# Console_Block.net
KiCad netlist of a schematic drawn in EAGLE
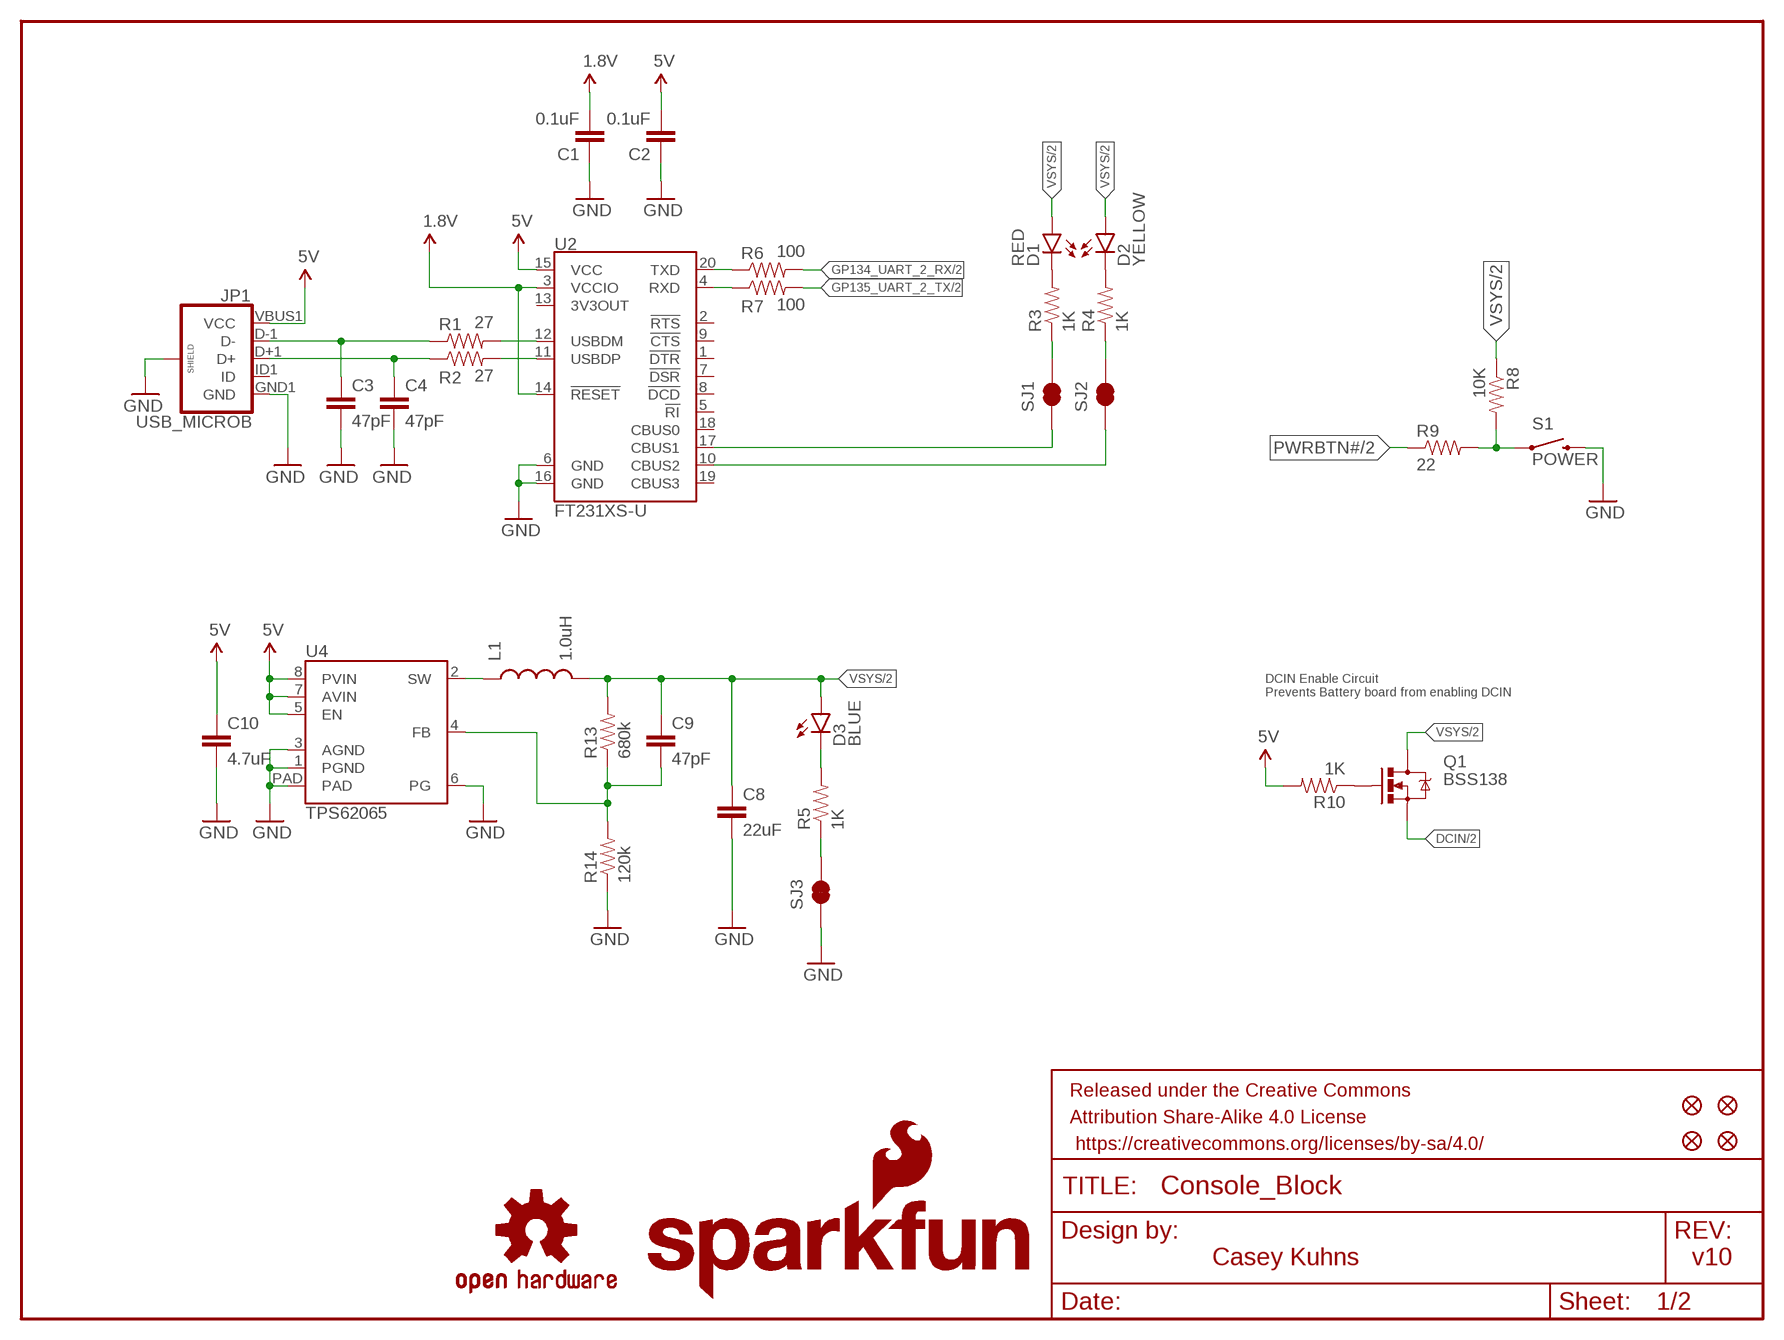
[diagram p0: schematic, sheet 1]
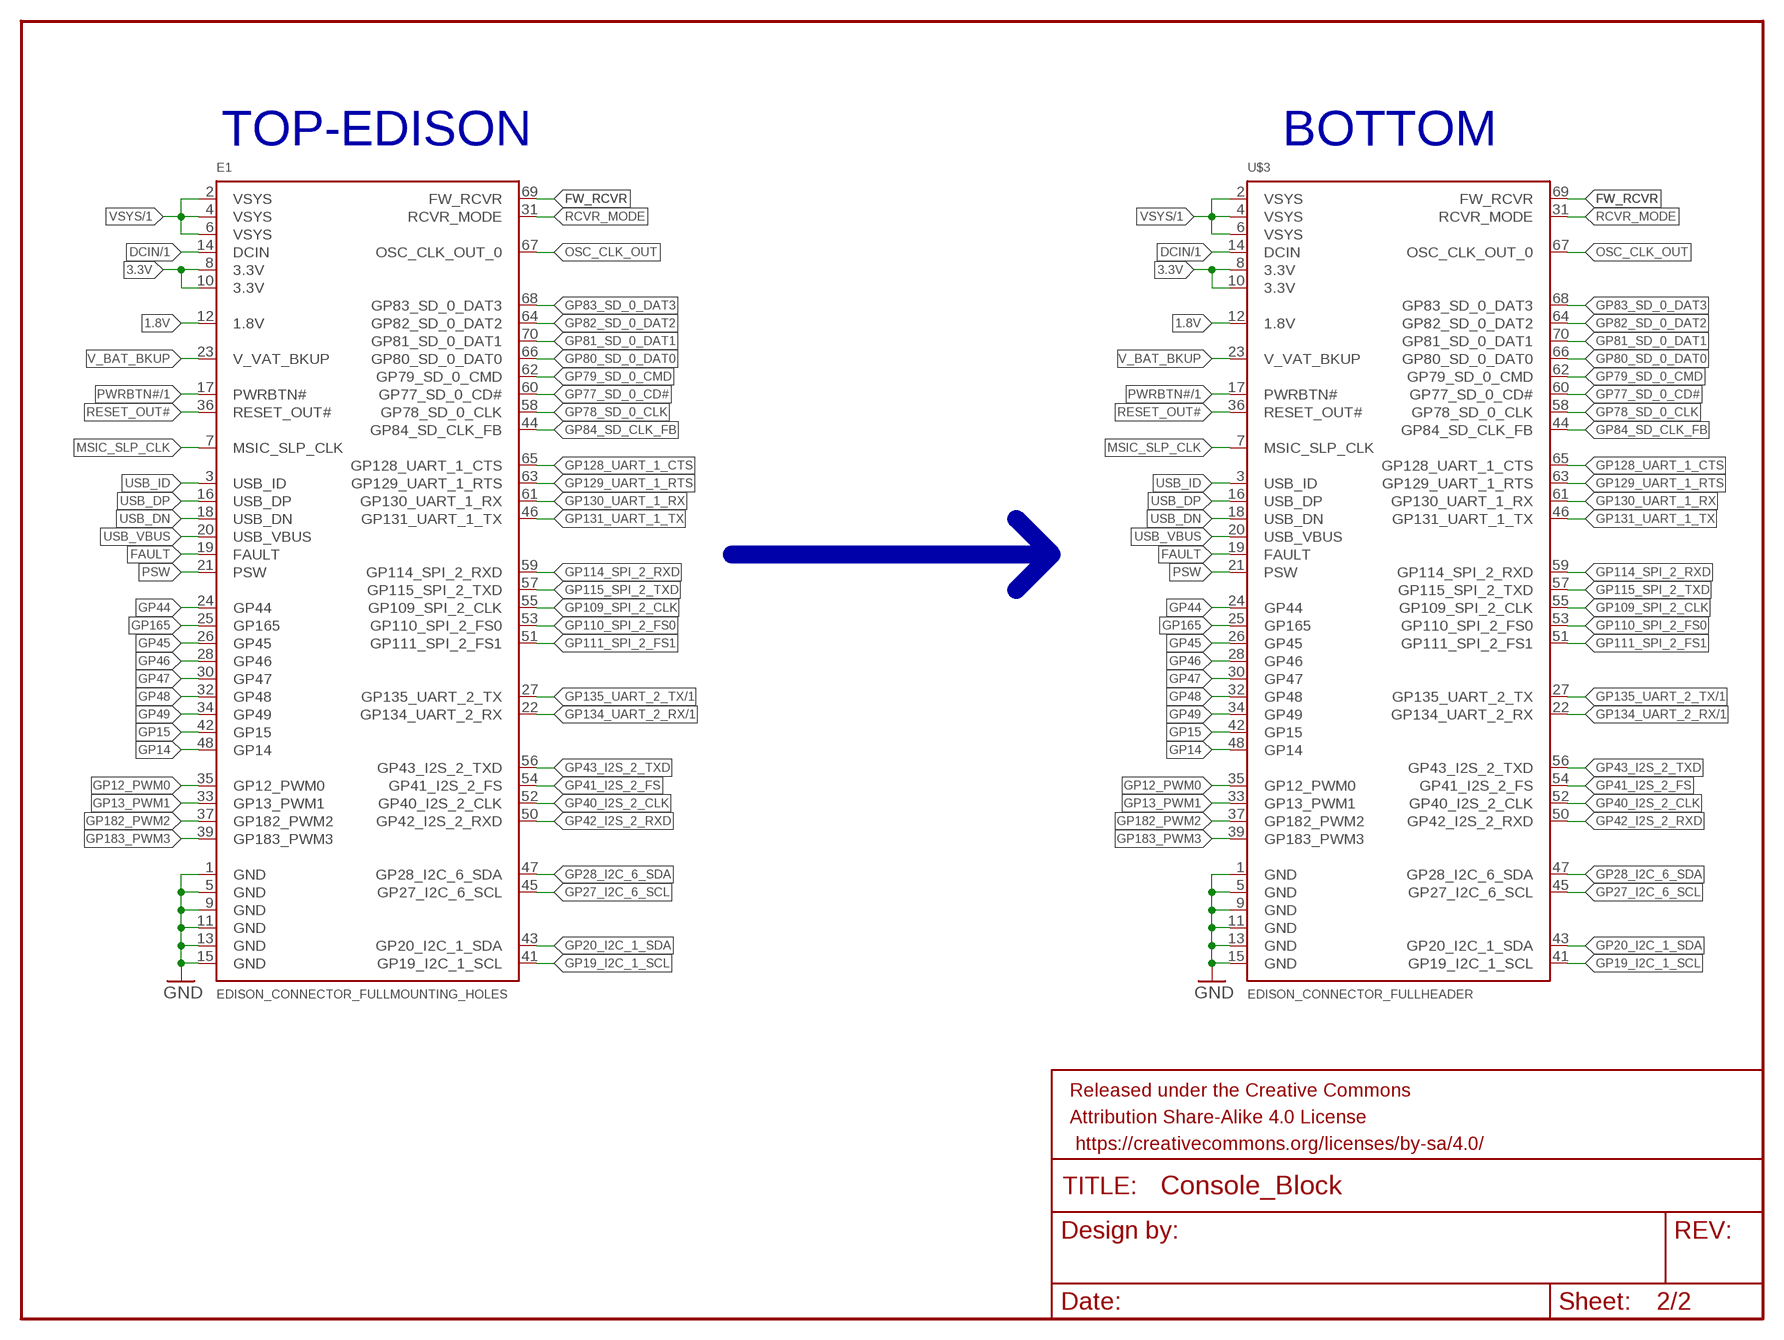
[diagram p1: schematic, sheet 2]

(export (version "E")
  (design (tool "Eeschema 10.0.6"))
  (components
    (comp (ref "E1")
      (value "EDISON_CONNECTOR_FULLMOUNTING_HOLES")
      (footprint "eagle-import:EDISON_DAUGHTER")
      (libsource (lib "eagle-import") (part "EDISON_CONNECTOR_FULLMOUNTING_HOLES"))
    )
    (comp (ref "FRAME2")
      (value "FRAME-LETTER")
      (footprint "eagle-import:CREATIVE_COMMONS")
      (libsource (lib "eagle-import") (part "FRAME-LETTER"))
    )
    (comp (ref "U$3")
      (value "EDISON_CONNECTOR_FULLHEADER")
      (footprint "eagle-import:DF40C-70DP-0.4(51)")
      (libsource (lib "eagle-import") (part "EDISON_CONNECTOR_FULLHEADER"))
    )
    (comp (ref "C1")
      (value "0.1uF")
      (footprint "eagle-import:0603-CAP")
      (libsource (lib "eagle-import") (part "0.1UF-25V-5%(0603)"))
    )
    (comp (ref "C2")
      (value "0.1uF")
      (footprint "eagle-import:0603-CAP")
      (libsource (lib "eagle-import") (part "0.1UF-25V-5%(0603)"))
    )
    (comp (ref "C3")
      (value "47pF")
      (footprint "eagle-import:0603-CAP")
      (libsource (lib "eagle-import") (part "47PF-50V-5%(0603)"))
    )
    (comp (ref "C4")
      (value "47pF")
      (footprint "eagle-import:0603-CAP")
      (libsource (lib "eagle-import") (part "47PF-50V-5%(0603)"))
    )
    (comp (ref "C8")
      (value "22uF")
      (footprint "eagle-import:0805")
      (libsource (lib "eagle-import") (part "22UF-6.3V-20%(0805)"))
    )
    (comp (ref "C9")
      (value "47pF")
      (footprint "eagle-import:0603-CAP")
      (libsource (lib "eagle-import") (part "47PF-50V-5%(0603)"))
    )
    (comp (ref "C10")
      (value "4.7uF")
      (footprint "eagle-import:0603-CAP")
      (libsource (lib "eagle-import") (part "4.7UF-6.3V-10%(0603)0603"))
    )
    (comp (ref "D1")
      (value "RED")
      (footprint "eagle-import:LED-0603")
      (libsource (lib "eagle-import") (part "LED-RED0603"))
    )
    (comp (ref "D2")
      (value "YELLOW")
      (footprint "eagle-import:LED-0603")
      (libsource (lib "eagle-import") (part "LED-YELLOW0603"))
    )
    (comp (ref "D3")
      (value "BLUE")
      (footprint "eagle-import:LED-0603")
      (libsource (lib "eagle-import") (part "LED-BLUE0603"))
    )
    (comp (ref "FID1")
      (value "FIDUCIAL1X2")
      (footprint "eagle-import:FIDUCIAL-1X2")
      (libsource (lib "eagle-import") (part "FIDUCIAL1X2"))
    )
    (comp (ref "FID2")
      (value "FIDUCIAL1X2")
      (footprint "eagle-import:FIDUCIAL-1X2")
      (libsource (lib "eagle-import") (part "FIDUCIAL1X2"))
    )
    (comp (ref "FID3")
      (value "FIDUCIAL1X2")
      (footprint "eagle-import:FIDUCIAL-1X2")
      (libsource (lib "eagle-import") (part "FIDUCIAL1X2"))
    )
    (comp (ref "FID4")
      (value "FIDUCIAL1X2")
      (footprint "eagle-import:FIDUCIAL-1X2")
      (libsource (lib "eagle-import") (part "FIDUCIAL1X2"))
    )
    (comp (ref "FRAME1")
      (value "FRAME-LETTER")
      (footprint "eagle-import:CREATIVE_COMMONS")
      (libsource (lib "eagle-import") (part "FRAME-LETTER"))
    )
    (comp (ref "JP1")
      (value "USB_MICROB")
      (footprint "eagle-import:USB-B-MICRO-SMD_V03")
      (libsource (lib "eagle-import") (part "USB_MICROB_PLUGCONN-11752"))
    )
    (comp (ref "L1")
      (value "1.0uH")
      (footprint "eagle-import:INDUCTOR-SRP4020")
      (libsource (lib "eagle-import") (part "INDUCTOR"))
    )
    (comp (ref "LOGO1")
      (value "SFE_LOGO_NAME_FLAME.1_INCH")
      (footprint "eagle-import:SFE_LOGO_NAME_FLAME_.1")
      (libsource (lib "eagle-import") (part "SFE_LOGO_NAME_FLAME.1_INCH"))
    )
    (comp (ref "LOGO4")
      (value "OSHW-LOGOS")
      (footprint "eagle-import:OSHW-LOGO-S")
      (libsource (lib "eagle-import") (part "OSHW-LOGOS"))
    )
    (comp (ref "Q1")
      (value "BSS138")
      (footprint "eagle-import:SOT23-3")
      (libsource (lib "eagle-import") (part "MOSFET-NCHANNELBSS138"))
    )
    (comp (ref "R1")
      (value "27")
      (footprint "eagle-import:0603")
      (libsource (lib "eagle-import") (part "27OHM1/10W1%(0603)"))
    )
    (comp (ref "R2")
      (value "27")
      (footprint "eagle-import:0603")
      (libsource (lib "eagle-import") (part "27OHM1/10W1%(0603)"))
    )
    (comp (ref "R3")
      (value "1K")
      (footprint "eagle-import:0603-RES")
      (libsource (lib "eagle-import") (part "1KOHM1/10W1%(0603)"))
    )
    (comp (ref "R4")
      (value "1K")
      (footprint "eagle-import:0603-RES")
      (libsource (lib "eagle-import") (part "1KOHM1/10W1%(0603)"))
    )
    (comp (ref "R5")
      (value "1K")
      (footprint "eagle-import:0603-RES")
      (libsource (lib "eagle-import") (part "1KOHM1/10W1%(0603)"))
    )
    (comp (ref "R6")
      (value "100")
      (footprint "eagle-import:0603-RES")
      (libsource (lib "eagle-import") (part "100OHM1/10W1%(0603)"))
    )
    (comp (ref "R7")
      (value "100")
      (footprint "eagle-import:0603-RES")
      (libsource (lib "eagle-import") (part "100OHM1/10W1%(0603)"))
    )
    (comp (ref "R8")
      (value "10K")
      (footprint "eagle-import:0603-RES")
      (libsource (lib "eagle-import") (part "10KOHM1/10W1%(0603)0603"))
    )
    (comp (ref "R9")
      (value "22")
      (footprint "eagle-import:0603-RES")
      (libsource (lib "eagle-import") (part "22OHM1/10W1%(0603)"))
    )
    (comp (ref "R10")
      (value "1K")
      (footprint "eagle-import:0603-RES")
      (libsource (lib "eagle-import") (part "1KOHM1/10W1%(0603)"))
    )
    (comp (ref "R13")
      (value "680k")
      (footprint "eagle-import:0603-RES")
      (libsource (lib "eagle-import") (part "RESISTOR0603"))
    )
    (comp (ref "R14")
      (value "120k")
      (footprint "eagle-import:0603-RES")
      (libsource (lib "eagle-import") (part "RESISTOR0603"))
    )
    (comp (ref "S1")
      (value "POWER")
      (footprint "eagle-import:TACTILE_SWITCH-SMD-RIGHT-ANGLE")
      (libsource (lib "eagle-import") (part "SWITCH-MOMENTARY-2TACTILE-SWITCH-SMD-RIGHT-ANGLE"))
    )
    (comp (ref "SJ1")
      (value "JUMPER-PAD-2-NC_BY_TRACE")
      (footprint "eagle-import:PAD-JUMPER-2-NC_BY_TRACE_YES_SILK")
      (libsource (lib "eagle-import") (part "JUMPER-PAD-2-NC_BY_TRACE"))
    )
    (comp (ref "SJ2")
      (value "JUMPER-PAD-2-NC_BY_TRACE")
      (footprint "eagle-import:PAD-JUMPER-2-NC_BY_TRACE_YES_SILK")
      (libsource (lib "eagle-import") (part "JUMPER-PAD-2-NC_BY_TRACE"))
    )
    (comp (ref "SJ3")
      (value "JUMPER-PAD-2-NC_BY_TRACE")
      (footprint "eagle-import:PAD-JUMPER-2-NC_BY_TRACE_YES_SILK")
      (libsource (lib "eagle-import") (part "JUMPER-PAD-2-NC_BY_TRACE"))
    )
    (comp (ref "U2")
      (value "FT231XS-U")
      (footprint "eagle-import:SSOP20_L")
      (libsource (lib "eagle-import") (part "FT231XS"))
    )
    (comp (ref "U4")
      (value "TPS62065")
      (footprint "eagle-import:WSON-8-PAD")
      (libsource (lib "eagle-import") (part "TPS62065"))
    )
  )
  (nets
    (net (code "1") (name "1.8V") (class "Default")
      (node (ref "C1") (pin "2") (pinfunction "2_2") (pintype "passive"))
      (node (ref "E1") (pin "12") (pinfunction "1.8V_12") (pintype "bidirectional"))
      (node (ref "U$3") (pin "12") (pinfunction "1.8V_12") (pintype "bidirectional"))
      (node (ref "U2") (pin "14") (pinfunction "~{RESET}_14") (pintype "bidirectional"))
      (node (ref "U2") (pin "3") (pinfunction "VCCIO_3") (pintype "bidirectional"))
    )
    (net (code "2") (name "3.3V") (class "Default")
      (node (ref "E1") (pin "10") (pinfunction "3.3V_10") (pintype "bidirectional"))
      (node (ref "E1") (pin "8") (pinfunction "3.3V_8") (pintype "bidirectional"))
      (node (ref "U$3") (pin "10") (pinfunction "3.3V_10") (pintype "bidirectional"))
      (node (ref "U$3") (pin "8") (pinfunction "3.3V_8") (pintype "bidirectional"))
    )
    (net (code "3") (name "5V") (class "Default")
      (node (ref "C10") (pin "1") (pinfunction "1_1") (pintype "passive"))
      (node (ref "C2") (pin "2") (pinfunction "2_2") (pintype "passive"))
      (node (ref "JP1") (pin "VBUS1") (pinfunction "VCC_VBUS1") (pintype "bidirectional"))
      (node (ref "R10") (pin "2") (pinfunction "2_2") (pintype "passive"))
      (node (ref "U2") (pin "15") (pinfunction "VCC_15") (pintype "bidirectional"))
      (node (ref "U4") (pin "5") (pinfunction "EN_5") (pintype "bidirectional"))
      (node (ref "U4") (pin "7") (pinfunction "AVIN_7") (pintype "bidirectional"))
      (node (ref "U4") (pin "8") (pinfunction "PVIN_8") (pintype "bidirectional"))
    )
    (net (code "4") (name "DCIN") (class "Default")
      (node (ref "E1") (pin "14") (pinfunction "DCIN_14") (pintype "bidirectional"))
      (node (ref "Q1") (pin "2") (pinfunction "S_2") (pintype "passive"))
      (node (ref "U$3") (pin "14") (pinfunction "DCIN_14") (pintype "bidirectional"))
    )
    (net (code "5") (name "FAULT") (class "Default")
      (node (ref "E1") (pin "19") (pinfunction "FAULT_19") (pintype "bidirectional"))
      (node (ref "U$3") (pin "19") (pinfunction "FAULT_19") (pintype "bidirectional"))
    )
    (net (code "6") (name "FW_RCVR") (class "Default")
      (node (ref "E1") (pin "69") (pinfunction "FW_RCVR_69") (pintype "bidirectional"))
      (node (ref "U$3") (pin "69") (pinfunction "FW_RCVR_69") (pintype "bidirectional"))
    )
    (net (code "7") (name "GND") (class "Default")
      (node (ref "C1") (pin "1") (pinfunction "1_1") (pintype "passive"))
      (node (ref "C10") (pin "2") (pinfunction "2_2") (pintype "passive"))
      (node (ref "C2") (pin "1") (pinfunction "1_1") (pintype "passive"))
      (node (ref "C3") (pin "2") (pinfunction "2_2") (pintype "passive"))
      (node (ref "C4") (pin "2") (pinfunction "2_2") (pintype "passive"))
      (node (ref "C8") (pin "2") (pinfunction "2_2") (pintype "passive"))
      (node (ref "E1") (pin "1") (pinfunction "GND_1") (pintype "bidirectional"))
      (node (ref "E1") (pin "11") (pinfunction "GND_11") (pintype "bidirectional"))
      (node (ref "E1") (pin "13") (pinfunction "GND_13") (pintype "bidirectional"))
      (node (ref "E1") (pin "15") (pinfunction "GND_15") (pintype "bidirectional"))
      (node (ref "E1") (pin "5") (pinfunction "GND_5") (pintype "bidirectional"))
      (node (ref "E1") (pin "9") (pinfunction "GND_9") (pintype "bidirectional"))
      (node (ref "JP1") (pin "GND1") (pinfunction "GND_GND1") (pintype "bidirectional"))
      (node (ref "JP1") (pin "SHIELD1") (pinfunction "SHIELD_SHIELD1") (pintype "bidirectional"))
      (node (ref "JP1") (pin "SHIELD2") (pinfunction "SHIELD_SHIELD2") (pintype "bidirectional"))
      (node (ref "JP1") (pin "SHIELD3") (pinfunction "SHIELD_SHIELD3") (pintype "bidirectional"))
      (node (ref "R14") (pin "1") (pinfunction "1_1") (pintype "passive"))
      (node (ref "S1") (pin "2") (pinfunction "2_2") (pintype "passive"))
      (node (ref "SJ3") (pin "1") (pinfunction "1_1") (pintype "passive"))
      (node (ref "U$3") (pin "1") (pinfunction "GND_1") (pintype "bidirectional"))
      (node (ref "U$3") (pin "11") (pinfunction "GND_11") (pintype "bidirectional"))
      (node (ref "U$3") (pin "13") (pinfunction "GND_13") (pintype "bidirectional"))
      (node (ref "U$3") (pin "15") (pinfunction "GND_15") (pintype "bidirectional"))
      (node (ref "U$3") (pin "5") (pinfunction "GND_5") (pintype "bidirectional"))
      (node (ref "U$3") (pin "9") (pinfunction "GND_9") (pintype "bidirectional"))
      (node (ref "U2") (pin "16") (pinfunction "GND_16") (pintype "bidirectional"))
      (node (ref "U2") (pin "6") (pinfunction "GND_6") (pintype "bidirectional"))
      (node (ref "U4") (pin "1") (pinfunction "PGND_1") (pintype "bidirectional"))
      (node (ref "U4") (pin "3") (pinfunction "AGND_3") (pintype "bidirectional"))
      (node (ref "U4") (pin "6") (pinfunction "PG_6") (pintype "bidirectional"))
      (node (ref "U4") (pin "PAD") (pinfunction "PAD_PAD") (pintype "bidirectional"))
    )
    (net (code "8") (name "GP12_PWM0") (class "Default")
      (node (ref "E1") (pin "35") (pinfunction "GP12_PWM0_35") (pintype "bidirectional"))
      (node (ref "U$3") (pin "35") (pinfunction "GP12_PWM0_35") (pintype "bidirectional"))
    )
    (net (code "9") (name "GP13_PWM1") (class "Default")
      (node (ref "E1") (pin "33") (pinfunction "GP13_PWM1_33") (pintype "bidirectional"))
      (node (ref "U$3") (pin "33") (pinfunction "GP13_PWM1_33") (pintype "bidirectional"))
    )
    (net (code "10") (name "GP14") (class "Default")
      (node (ref "E1") (pin "48") (pinfunction "GP14_48") (pintype "bidirectional"))
      (node (ref "U$3") (pin "48") (pinfunction "GP14_48") (pintype "bidirectional"))
    )
    (net (code "11") (name "GP15") (class "Default")
      (node (ref "E1") (pin "42") (pinfunction "GP15_42") (pintype "bidirectional"))
      (node (ref "U$3") (pin "42") (pinfunction "GP15_42") (pintype "bidirectional"))
    )
    (net (code "12") (name "GP19_I2C_1_SCL") (class "Default")
      (node (ref "E1") (pin "41") (pinfunction "GP19_I2C_1_SCL_41") (pintype "bidirectional"))
      (node (ref "U$3") (pin "41") (pinfunction "GP19_I2C_1_SCL_41") (pintype "bidirectional"))
    )
    (net (code "13") (name "GP20_I2C_1_SDA") (class "Default")
      (node (ref "E1") (pin "43") (pinfunction "GP20_I2C_1_SDA_43") (pintype "bidirectional"))
      (node (ref "U$3") (pin "43") (pinfunction "GP20_I2C_1_SDA_43") (pintype "bidirectional"))
    )
    (net (code "14") (name "GP27_I2C_6_SCL") (class "Default")
      (node (ref "E1") (pin "45") (pinfunction "GP27_I2C_6_SCL_45") (pintype "bidirectional"))
      (node (ref "U$3") (pin "45") (pinfunction "GP27_I2C_6_SCL_45") (pintype "bidirectional"))
    )
    (net (code "15") (name "GP28_I2C_6_SDA") (class "Default")
      (node (ref "E1") (pin "47") (pinfunction "GP28_I2C_6_SDA_47") (pintype "bidirectional"))
      (node (ref "U$3") (pin "47") (pinfunction "GP28_I2C_6_SDA_47") (pintype "bidirectional"))
    )
    (net (code "16") (name "GP40_I2S_2_CLK") (class "Default")
      (node (ref "E1") (pin "52") (pinfunction "GP40_I2S_2_CLK_52") (pintype "bidirectional"))
      (node (ref "U$3") (pin "52") (pinfunction "GP40_I2S_2_CLK_52") (pintype "bidirectional"))
    )
    (net (code "17") (name "GP41_I2S_2_FS") (class "Default")
      (node (ref "E1") (pin "54") (pinfunction "GP41_I2S_2_FS_54") (pintype "bidirectional"))
      (node (ref "U$3") (pin "54") (pinfunction "GP41_I2S_2_FS_54") (pintype "bidirectional"))
    )
    (net (code "18") (name "GP42_I2S_2_RXD") (class "Default")
      (node (ref "E1") (pin "50") (pinfunction "GP42_I2S_2_RXD_50") (pintype "bidirectional"))
      (node (ref "U$3") (pin "50") (pinfunction "GP42_I2S_2_RXD_50") (pintype "bidirectional"))
    )
    (net (code "19") (name "GP43_I2S_2_TXD") (class "Default")
      (node (ref "E1") (pin "56") (pinfunction "GP43_I2S_2_TXD_56") (pintype "bidirectional"))
      (node (ref "U$3") (pin "56") (pinfunction "GP43_I2S_2_TXD_56") (pintype "bidirectional"))
    )
    (net (code "20") (name "GP44") (class "Default")
      (node (ref "E1") (pin "24") (pinfunction "GP44_24") (pintype "bidirectional"))
      (node (ref "U$3") (pin "24") (pinfunction "GP44_24") (pintype "bidirectional"))
    )
    (net (code "21") (name "GP45") (class "Default")
      (node (ref "E1") (pin "26") (pinfunction "GP45_26") (pintype "bidirectional"))
      (node (ref "U$3") (pin "26") (pinfunction "GP45_26") (pintype "bidirectional"))
    )
    (net (code "22") (name "GP46") (class "Default")
      (node (ref "E1") (pin "28") (pinfunction "GP46_28") (pintype "bidirectional"))
      (node (ref "U$3") (pin "28") (pinfunction "GP46_28") (pintype "bidirectional"))
    )
    (net (code "23") (name "GP47") (class "Default")
      (node (ref "E1") (pin "30") (pinfunction "GP47_30") (pintype "bidirectional"))
      (node (ref "U$3") (pin "30") (pinfunction "GP47_30") (pintype "bidirectional"))
    )
    (net (code "24") (name "GP48") (class "Default")
      (node (ref "E1") (pin "32") (pinfunction "GP48_32") (pintype "bidirectional"))
      (node (ref "U$3") (pin "32") (pinfunction "GP48_32") (pintype "bidirectional"))
    )
    (net (code "25") (name "GP49") (class "Default")
      (node (ref "E1") (pin "34") (pinfunction "GP49_34") (pintype "bidirectional"))
      (node (ref "U$3") (pin "34") (pinfunction "GP49_34") (pintype "bidirectional"))
    )
    (net (code "26") (name "GP77_SD_0_CD#") (class "Default")
      (node (ref "E1") (pin "60") (pinfunction "GP77_SD_0_CD#_60") (pintype "bidirectional"))
      (node (ref "U$3") (pin "60") (pinfunction "GP77_SD_0_CD#_60") (pintype "bidirectional"))
    )
    (net (code "27") (name "GP78_SD_0_CLK") (class "Default")
      (node (ref "E1") (pin "58") (pinfunction "GP78_SD_0_CLK_58") (pintype "bidirectional"))
      (node (ref "U$3") (pin "58") (pinfunction "GP78_SD_0_CLK_58") (pintype "bidirectional"))
    )
    (net (code "28") (name "GP79_SD_0_CMD") (class "Default")
      (node (ref "E1") (pin "62") (pinfunction "GP79_SD_0_CMD_62") (pintype "bidirectional"))
      (node (ref "U$3") (pin "62") (pinfunction "GP79_SD_0_CMD_62") (pintype "bidirectional"))
    )
    (net (code "29") (name "GP80_SD_0_DAT0") (class "Default")
      (node (ref "E1") (pin "66") (pinfunction "GP80_SD_0_DAT0_66") (pintype "bidirectional"))
      (node (ref "U$3") (pin "66") (pinfunction "GP80_SD_0_DAT0_66") (pintype "bidirectional"))
    )
    (net (code "30") (name "GP81_SD_0_DAT1") (class "Default")
      (node (ref "E1") (pin "70") (pinfunction "GP81_SD_0_DAT1_70") (pintype "bidirectional"))
      (node (ref "U$3") (pin "70") (pinfunction "GP81_SD_0_DAT1_70") (pintype "bidirectional"))
    )
    (net (code "31") (name "GP82_SD_0_DAT2") (class "Default")
      (node (ref "E1") (pin "64") (pinfunction "GP82_SD_0_DAT2_64") (pintype "bidirectional"))
      (node (ref "U$3") (pin "64") (pinfunction "GP82_SD_0_DAT2_64") (pintype "bidirectional"))
    )
    (net (code "32") (name "GP83_SD_0_DAT3") (class "Default")
      (node (ref "E1") (pin "68") (pinfunction "GP83_SD_0_DAT3_68") (pintype "bidirectional"))
      (node (ref "U$3") (pin "68") (pinfunction "GP83_SD_0_DAT3_68") (pintype "bidirectional"))
    )
    (net (code "33") (name "GP84_SD_CLK_FB") (class "Default")
      (node (ref "E1") (pin "44") (pinfunction "GP84_SD_CLK_FB_44") (pintype "bidirectional"))
      (node (ref "U$3") (pin "44") (pinfunction "GP84_SD_CLK_FB_44") (pintype "bidirectional"))
    )
    (net (code "34") (name "GP109_SPI_2_CLK") (class "Default")
      (node (ref "E1") (pin "55") (pinfunction "GP109_SPI_2_CLK_55") (pintype "bidirectional"))
      (node (ref "U$3") (pin "55") (pinfunction "GP109_SPI_2_CLK_55") (pintype "bidirectional"))
    )
    (net (code "35") (name "GP110_SPI_2_FS0") (class "Default")
      (node (ref "E1") (pin "53") (pinfunction "GP110_SPI_2_FS0_53") (pintype "bidirectional"))
      (node (ref "U$3") (pin "53") (pinfunction "GP110_SPI_2_FS0_53") (pintype "bidirectional"))
    )
    (net (code "36") (name "GP111_SPI_2_FS1") (class "Default")
      (node (ref "E1") (pin "51") (pinfunction "GP111_SPI_2_FS1_51") (pintype "bidirectional"))
      (node (ref "U$3") (pin "51") (pinfunction "GP111_SPI_2_FS1_51") (pintype "bidirectional"))
    )
    (net (code "37") (name "GP114_SPI_2_RXD") (class "Default")
      (node (ref "E1") (pin "59") (pinfunction "GP114_SPI_2_RXD_59") (pintype "bidirectional"))
      (node (ref "U$3") (pin "59") (pinfunction "GP114_SPI_2_RXD_59") (pintype "bidirectional"))
    )
    (net (code "38") (name "GP115_SPI_2_TXD") (class "Default")
      (node (ref "E1") (pin "57") (pinfunction "GP115_SPI_2_TXD_57") (pintype "bidirectional"))
      (node (ref "U$3") (pin "57") (pinfunction "GP115_SPI_2_TXD_57") (pintype "bidirectional"))
    )
    (net (code "39") (name "GP128_UART_1_CTS") (class "Default")
      (node (ref "E1") (pin "65") (pinfunction "GP128_UART_1_CTS_65") (pintype "bidirectional"))
      (node (ref "U$3") (pin "65") (pinfunction "GP128_UART_1_CTS_65") (pintype "bidirectional"))
    )
    (net (code "40") (name "GP129_UART_1_RTS") (class "Default")
      (node (ref "E1") (pin "63") (pinfunction "GP129_UART_1_RTS_63") (pintype "bidirectional"))
      (node (ref "U$3") (pin "63") (pinfunction "GP129_UART_1_RTS_63") (pintype "bidirectional"))
    )
    (net (code "41") (name "GP130_UART_1_RX") (class "Default")
      (node (ref "E1") (pin "61") (pinfunction "GP130_UART_1_RX_61") (pintype "bidirectional"))
      (node (ref "U$3") (pin "61") (pinfunction "GP130_UART_1_RX_61") (pintype "bidirectional"))
    )
    (net (code "42") (name "GP131_UART_1_TX") (class "Default")
      (node (ref "E1") (pin "46") (pinfunction "GP131_UART_1_TX_46") (pintype "bidirectional"))
      (node (ref "U$3") (pin "46") (pinfunction "GP131_UART_1_TX_46") (pintype "bidirectional"))
    )
    (net (code "43") (name "GP134_UART_2_RX") (class "Default")
      (node (ref "E1") (pin "22") (pinfunction "GP134_UART_2_RX_22") (pintype "bidirectional"))
      (node (ref "R6") (pin "2") (pinfunction "2_2") (pintype "passive"))
      (node (ref "U$3") (pin "22") (pinfunction "GP134_UART_2_RX_22") (pintype "bidirectional"))
    )
    (net (code "44") (name "GP135_UART_2_TX") (class "Default")
      (node (ref "E1") (pin "27") (pinfunction "GP135_UART_2_TX_27") (pintype "bidirectional"))
      (node (ref "R7") (pin "2") (pinfunction "2_2") (pintype "passive"))
      (node (ref "U$3") (pin "27") (pinfunction "GP135_UART_2_TX_27") (pintype "bidirectional"))
    )
    (net (code "45") (name "GP165") (class "Default")
      (node (ref "E1") (pin "25") (pinfunction "GP165_25") (pintype "bidirectional"))
      (node (ref "U$3") (pin "25") (pinfunction "GP165_25") (pintype "bidirectional"))
    )
    (net (code "46") (name "GP182_PWM2") (class "Default")
      (node (ref "E1") (pin "37") (pinfunction "GP182_PWM2_37") (pintype "bidirectional"))
      (node (ref "U$3") (pin "37") (pinfunction "GP182_PWM2_37") (pintype "bidirectional"))
    )
    (net (code "47") (name "GP183_PWM3") (class "Default")
      (node (ref "E1") (pin "39") (pinfunction "GP183_PWM3_39") (pintype "bidirectional"))
      (node (ref "U$3") (pin "39") (pinfunction "GP183_PWM3_39") (pintype "bidirectional"))
    )
    (net (code "48") (name "MSIC_SLP_CLK") (class "Default")
      (node (ref "E1") (pin "7") (pinfunction "MSIC_SLP_CLK_7") (pintype "bidirectional"))
      (node (ref "U$3") (pin "7") (pinfunction "MSIC_SLP_CLK_7") (pintype "bidirectional"))
    )
    (net (code "49") (name "Net-(D1-PadC)") (class "Default")
      (node (ref "D1") (pin "C") (pinfunction "C_C") (pintype "passive"))
      (node (ref "R3") (pin "2") (pinfunction "2_2") (pintype "passive"))
    )
    (net (code "50") (name "Net-(D2-PadC)") (class "Default")
      (node (ref "D2") (pin "C") (pinfunction "C_C") (pintype "passive"))
      (node (ref "R4") (pin "2") (pinfunction "2_2") (pintype "passive"))
    )
    (net (code "51") (name "Net-(D3-PadC)") (class "Default")
      (node (ref "D3") (pin "C") (pinfunction "C_C") (pintype "passive"))
      (node (ref "R5") (pin "2") (pinfunction "2_2") (pintype "passive"))
    )
    (net (code "52") (name "Net-(JP1-D+)") (class "Default")
      (node (ref "C4") (pin "1") (pinfunction "1_1") (pintype "passive"))
      (node (ref "JP1") (pin "D+1") (pinfunction "D+_D+1") (pintype "bidirectional"))
      (node (ref "R2") (pin "1") (pinfunction "1_1") (pintype "passive"))
    )
    (net (code "53") (name "Net-(JP1-D-)") (class "Default")
      (node (ref "C3") (pin "1") (pinfunction "1_1") (pintype "passive"))
      (node (ref "JP1") (pin "D-1") (pinfunction "D-_D-1") (pintype "bidirectional"))
      (node (ref "R1") (pin "1") (pinfunction "1_1") (pintype "passive"))
    )
    (net (code "54") (name "Net-(L1-1)") (class "Default")
      (node (ref "L1") (pin "P$1") (pinfunction "1_P$1") (pintype "passive"))
      (node (ref "U4") (pin "2") (pinfunction "SW_2") (pintype "bidirectional"))
    )
    (net (code "55") (name "Net-(Q1-G)") (class "Default")
      (node (ref "Q1") (pin "1") (pinfunction "G_1") (pintype "passive"))
      (node (ref "R10") (pin "1") (pinfunction "1_1") (pintype "passive"))
    )
    (net (code "56") (name "Net-(R3-Pad1)") (class "Default")
      (node (ref "R3") (pin "1") (pinfunction "1_1") (pintype "passive"))
      (node (ref "SJ1") (pin "2") (pinfunction "2_2") (pintype "passive"))
    )
    (net (code "57") (name "Net-(R4-Pad1)") (class "Default")
      (node (ref "R4") (pin "1") (pinfunction "1_1") (pintype "passive"))
      (node (ref "SJ2") (pin "2") (pinfunction "2_2") (pintype "passive"))
    )
    (net (code "58") (name "Net-(R5-Pad1)") (class "Default")
      (node (ref "R5") (pin "1") (pinfunction "1_1") (pintype "passive"))
      (node (ref "SJ3") (pin "2") (pinfunction "2_2") (pintype "passive"))
    )
    (net (code "59") (name "Net-(R8-Pad2)") (class "Default")
      (node (ref "R8") (pin "2") (pinfunction "2_2") (pintype "passive"))
      (node (ref "R9") (pin "2") (pinfunction "2_2") (pintype "passive"))
      (node (ref "S1") (pin "1") (pinfunction "1_1") (pintype "passive"))
    )
    (net (code "60") (name "Net-(U2-CBUS1)") (class "Default")
      (node (ref "SJ1") (pin "1") (pinfunction "1_1") (pintype "passive"))
      (node (ref "U2") (pin "17") (pinfunction "CBUS1_17") (pintype "bidirectional"))
    )
    (net (code "61") (name "Net-(U2-CBUS2)") (class "Default")
      (node (ref "SJ2") (pin "1") (pinfunction "1_1") (pintype "passive"))
      (node (ref "U2") (pin "10") (pinfunction "CBUS2_10") (pintype "bidirectional"))
    )
    (net (code "62") (name "Net-(U2-RXD)") (class "Default")
      (node (ref "R7") (pin "1") (pinfunction "1_1") (pintype "passive"))
      (node (ref "U2") (pin "4") (pinfunction "RXD_4") (pintype "bidirectional"))
    )
    (net (code "63") (name "Net-(U2-TXD)") (class "Default")
      (node (ref "R6") (pin "1") (pinfunction "1_1") (pintype "passive"))
      (node (ref "U2") (pin "20") (pinfunction "TXD_20") (pintype "bidirectional"))
    )
    (net (code "64") (name "Net-(U2-USBDM)") (class "Default")
      (node (ref "R1") (pin "2") (pinfunction "2_2") (pintype "passive"))
      (node (ref "U2") (pin "12") (pinfunction "USBDM_12") (pintype "bidirectional"))
    )
    (net (code "65") (name "Net-(U2-USBDP)") (class "Default")
      (node (ref "R2") (pin "2") (pinfunction "2_2") (pintype "passive"))
      (node (ref "U2") (pin "11") (pinfunction "USBDP_11") (pintype "bidirectional"))
    )
    (net (code "66") (name "Net-(U4-FB)") (class "Default")
      (node (ref "C9") (pin "2") (pinfunction "2_2") (pintype "passive"))
      (node (ref "R13") (pin "1") (pinfunction "1_1") (pintype "passive"))
      (node (ref "R14") (pin "2") (pinfunction "2_2") (pintype "passive"))
      (node (ref "U4") (pin "4") (pinfunction "FB_4") (pintype "bidirectional"))
    )
    (net (code "67") (name "OSC_CLK_OUT") (class "Default")
      (node (ref "E1") (pin "67") (pinfunction "OSC_CLK_OUT_0_67") (pintype "bidirectional"))
      (node (ref "U$3") (pin "67") (pinfunction "OSC_CLK_OUT_0_67") (pintype "bidirectional"))
    )
    (net (code "68") (name "PSW") (class "Default")
      (node (ref "E1") (pin "21") (pinfunction "PSW_21") (pintype "bidirectional"))
      (node (ref "U$3") (pin "21") (pinfunction "PSW_21") (pintype "bidirectional"))
    )
    (net (code "69") (name "PWRBTN#") (class "Default")
      (node (ref "E1") (pin "17") (pinfunction "PWRBTN#_17") (pintype "bidirectional"))
      (node (ref "R9") (pin "1") (pinfunction "1_1") (pintype "passive"))
      (node (ref "U$3") (pin "17") (pinfunction "PWRBTN#_17") (pintype "bidirectional"))
    )
    (net (code "70") (name "RCVR_MODE") (class "Default")
      (node (ref "E1") (pin "31") (pinfunction "RCVR_MODE_31") (pintype "bidirectional"))
      (node (ref "U$3") (pin "31") (pinfunction "RCVR_MODE_31") (pintype "bidirectional"))
    )
    (net (code "71") (name "RESET_OUT#") (class "Default")
      (node (ref "E1") (pin "36") (pinfunction "RESET_OUT#_36") (pintype "bidirectional"))
      (node (ref "U$3") (pin "36") (pinfunction "RESET_OUT#_36") (pintype "bidirectional"))
    )
    (net (code "72") (name "USB_DN") (class "Default")
      (node (ref "E1") (pin "18") (pinfunction "USB_DN_18") (pintype "bidirectional"))
      (node (ref "U$3") (pin "18") (pinfunction "USB_DN_18") (pintype "bidirectional"))
    )
    (net (code "73") (name "USB_DP") (class "Default")
      (node (ref "E1") (pin "16") (pinfunction "USB_DP_16") (pintype "bidirectional"))
      (node (ref "U$3") (pin "16") (pinfunction "USB_DP_16") (pintype "bidirectional"))
    )
    (net (code "74") (name "USB_ID") (class "Default")
      (node (ref "E1") (pin "3") (pinfunction "USB_ID_3") (pintype "bidirectional"))
      (node (ref "U$3") (pin "3") (pinfunction "USB_ID_3") (pintype "bidirectional"))
    )
    (net (code "75") (name "USB_VBUS") (class "Default")
      (node (ref "E1") (pin "20") (pinfunction "USB_VBUS_20") (pintype "bidirectional"))
      (node (ref "U$3") (pin "20") (pinfunction "USB_VBUS_20") (pintype "bidirectional"))
    )
    (net (code "76") (name "VSYS") (class "Default")
      (node (ref "C8") (pin "1") (pinfunction "1_1") (pintype "passive"))
      (node (ref "C9") (pin "1") (pinfunction "1_1") (pintype "passive"))
      (node (ref "D1") (pin "A") (pinfunction "A_A") (pintype "passive"))
      (node (ref "D2") (pin "A") (pinfunction "A_A") (pintype "passive"))
      (node (ref "D3") (pin "A") (pinfunction "A_A") (pintype "passive"))
      (node (ref "E1") (pin "2") (pinfunction "VSYS_2") (pintype "bidirectional"))
      (node (ref "E1") (pin "4") (pinfunction "VSYS_4") (pintype "bidirectional"))
      (node (ref "E1") (pin "6") (pinfunction "VSYS_6") (pintype "bidirectional"))
      (node (ref "L1") (pin "P$2") (pinfunction "2_P$2") (pintype "passive"))
      (node (ref "Q1") (pin "3") (pinfunction "D_3") (pintype "passive"))
      (node (ref "R13") (pin "2") (pinfunction "2_2") (pintype "passive"))
      (node (ref "R8") (pin "1") (pinfunction "1_1") (pintype "passive"))
      (node (ref "U$3") (pin "2") (pinfunction "VSYS_2") (pintype "bidirectional"))
      (node (ref "U$3") (pin "4") (pinfunction "VSYS_4") (pintype "bidirectional"))
      (node (ref "U$3") (pin "6") (pinfunction "VSYS_6") (pintype "bidirectional"))
    )
    (net (code "77") (name "V_BAT_BKUP") (class "Default")
      (node (ref "E1") (pin "23") (pinfunction "V_VAT_BKUP_23") (pintype "bidirectional"))
      (node (ref "U$3") (pin "23") (pinfunction "V_VAT_BKUP_23") (pintype "bidirectional"))
    )
    (net (code "78") (name "unconnected-(JP1-ID-PadID1)") (class "Default")
      (node (ref "JP1") (pin "ID1") (pinfunction "ID_ID1") (pintype "bidirectional"))
    )
    (net (code "79") (name "unconnected-(U2-3V3OUT-Pad13)") (class "Default")
      (node (ref "U2") (pin "13") (pinfunction "3V3OUT_13") (pintype "bidirectional"))
    )
    (net (code "80") (name "unconnected-(U2-CBUS0-Pad18)") (class "Default")
      (node (ref "U2") (pin "18") (pinfunction "CBUS0_18") (pintype "bidirectional"))
    )
    (net (code "81") (name "unconnected-(U2-CBUS3-Pad19)") (class "Default")
      (node (ref "U2") (pin "19") (pinfunction "CBUS3_19") (pintype "bidirectional"))
    )
    (net (code "82") (name "unconnected-(U2-~{CTS}-Pad9)") (class "Default")
      (node (ref "U2") (pin "9") (pinfunction "~{CTS}_9") (pintype "bidirectional"))
    )
    (net (code "83") (name "unconnected-(U2-~{DCD}-Pad8)") (class "Default")
      (node (ref "U2") (pin "8") (pinfunction "~{DCD}_8") (pintype "bidirectional"))
    )
    (net (code "84") (name "unconnected-(U2-~{DSR}-Pad7)") (class "Default")
      (node (ref "U2") (pin "7") (pinfunction "~{DSR}_7") (pintype "bidirectional"))
    )
    (net (code "85") (name "unconnected-(U2-~{DTR}-Pad1)") (class "Default")
      (node (ref "U2") (pin "1") (pinfunction "~{DTR}_1") (pintype "bidirectional"))
    )
    (net (code "86") (name "unconnected-(U2-~{RI}-Pad5)") (class "Default")
      (node (ref "U2") (pin "5") (pinfunction "~{RI}_5") (pintype "bidirectional"))
    )
    (net (code "87") (name "unconnected-(U2-~{RTS}-Pad2)") (class "Default")
      (node (ref "U2") (pin "2") (pinfunction "~{RTS}_2") (pintype "bidirectional"))
    )
  )
)
